# Tweetronic_Relay_Board.net
KiCad netlist of a schematic drawn in EAGLE
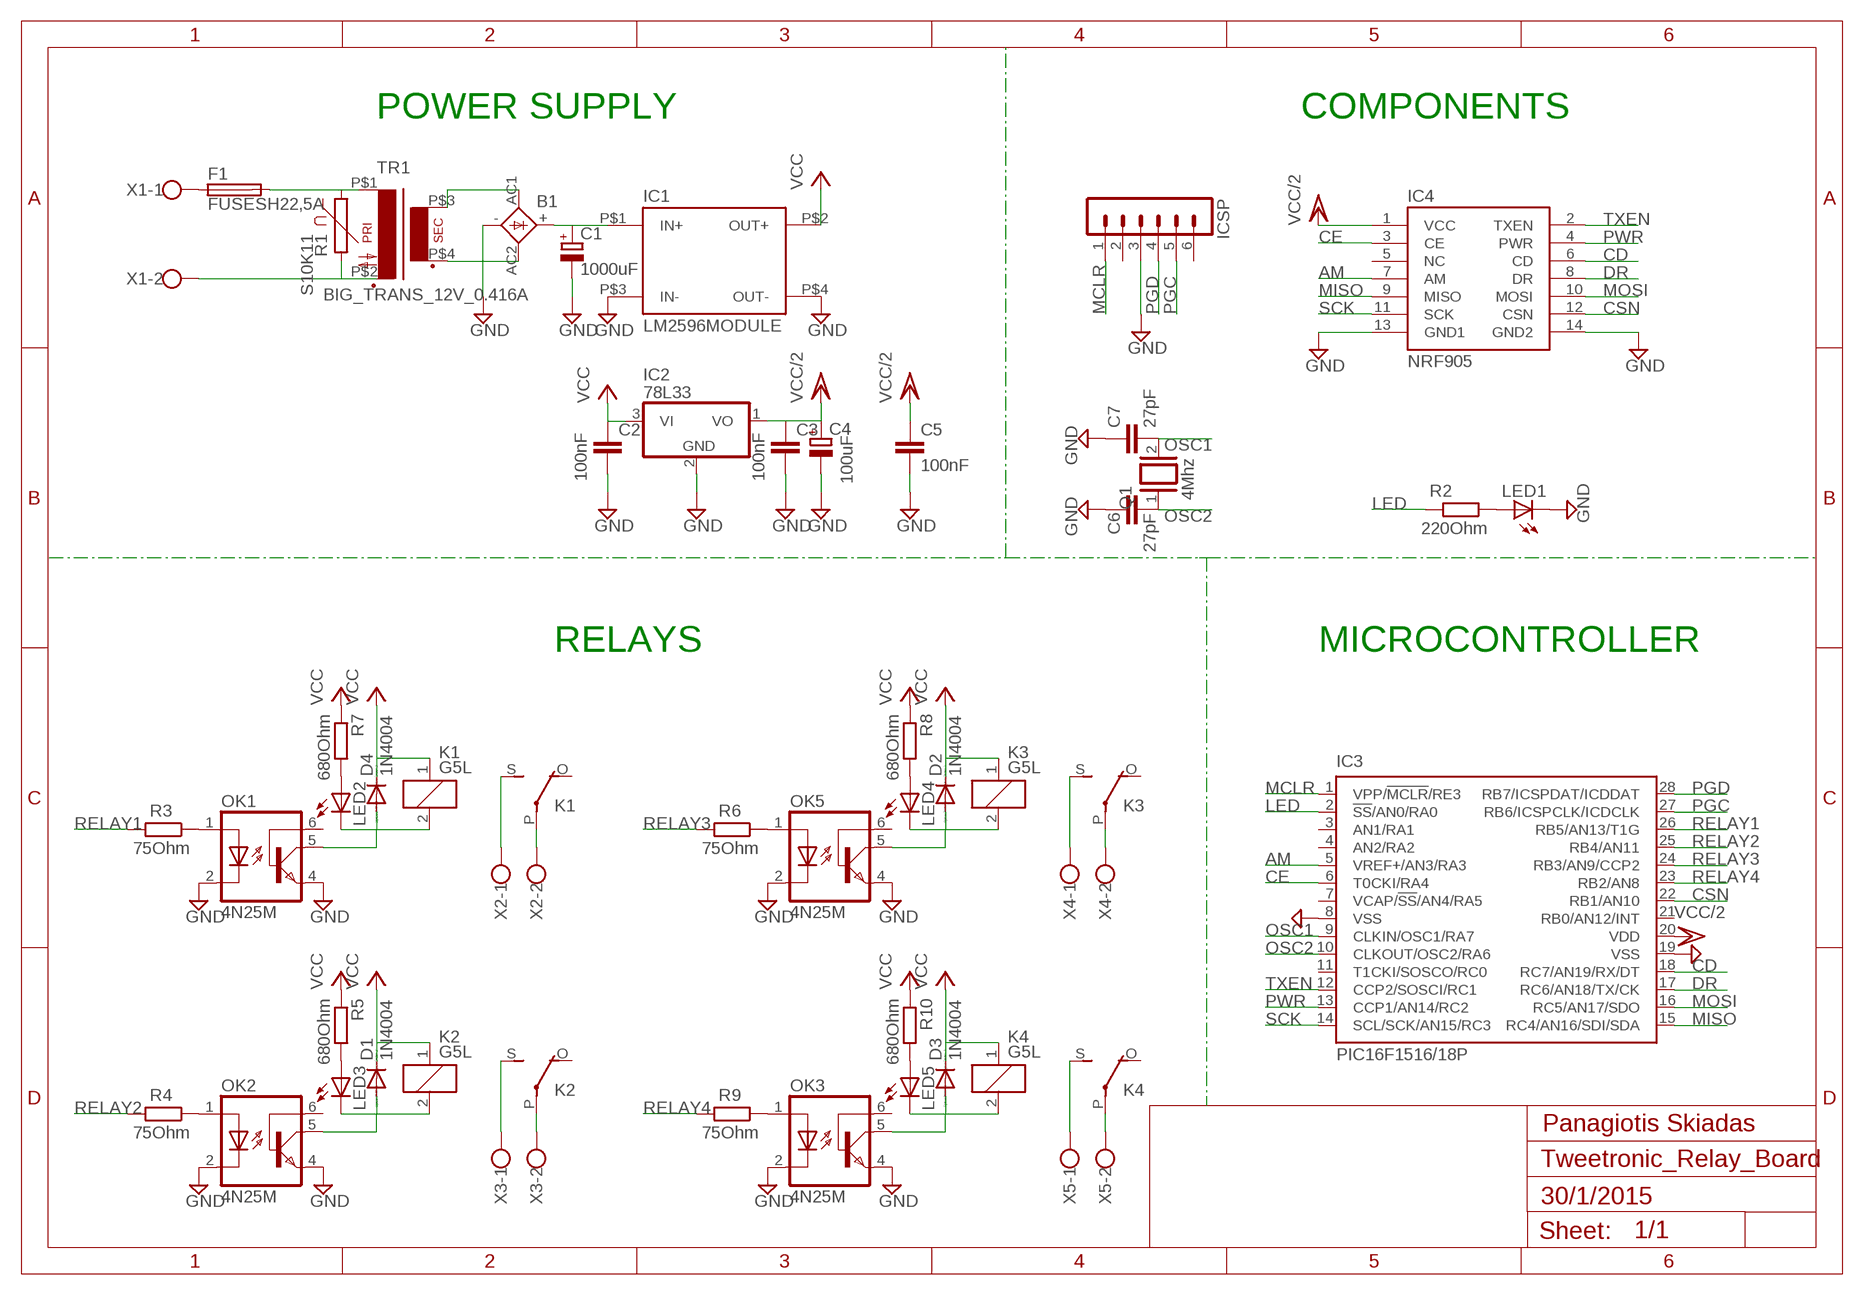
[diagram p0: schematic, sheet 1]

(export (version "E")
  (design (tool "Eeschema 10.0.6"))
  (components
    (comp (ref "B1")
      (value "1KAB")
      (footprint "eagle-import:1KAB")
      (libsource (lib "eagle-import") (part "1KAB"))
    )
    (comp (ref "C1")
      (value "1000uF")
      (footprint "eagle-import:E5-13")
      (libsource (lib "eagle-import") (part "CPOL-EUE5-13"))
    )
    (comp (ref "C2")
      (value "100nF")
      (footprint "eagle-import:C5B3")
      (libsource (lib "eagle-import") (part "C5/3"))
    )
    (comp (ref "C3")
      (value "100nF")
      (footprint "eagle-import:C5B3")
      (libsource (lib "eagle-import") (part "C5/3"))
    )
    (comp (ref "C4")
      (value "100uF")
      (footprint "eagle-import:E3,5-8")
      (libsource (lib "eagle-import") (part "CPOL-EUE3.5-8"))
    )
    (comp (ref "C5")
      (value "100nF")
      (footprint "eagle-import:C5B3")
      (libsource (lib "eagle-import") (part "C5/3"))
    )
    (comp (ref "C6")
      (value "27pF")
      (footprint "eagle-import:C2.5-3")
      (libsource (lib "eagle-import") (part "C2,5-3"))
    )
    (comp (ref "C7")
      (value "27pF")
      (footprint "eagle-import:C2.5-3")
      (libsource (lib "eagle-import") (part "C2,5-3"))
    )
    (comp (ref "D1")
      (value "1N4004")
      (footprint "eagle-import:DO41-10")
      (libsource (lib "eagle-import") (part "1N4004"))
    )
    (comp (ref "D2")
      (value "1N4004")
      (footprint "eagle-import:DO41-10")
      (libsource (lib "eagle-import") (part "1N4004"))
    )
    (comp (ref "D3")
      (value "1N4004")
      (footprint "eagle-import:DO41-10")
      (libsource (lib "eagle-import") (part "1N4004"))
    )
    (comp (ref "D4")
      (value "1N4004")
      (footprint "eagle-import:DO41-10")
      (libsource (lib "eagle-import") (part "1N4004"))
    )
    (comp (ref "F1")
      (value "FUSESH22,5A")
      (footprint "eagle-import:SH22,5A")
      (libsource (lib "eagle-import") (part "FUSESH22,5A"))
    )
    (comp (ref "IC1")
      (value "LM2596MODULE")
      (footprint "eagle-import:MODULE")
      (libsource (lib "eagle-import") (part "LM2596MODULE"))
    )
    (comp (ref "IC2")
      (value "78L33")
      (footprint "eagle-import:TO92")
      (libsource (lib "eagle-import") (part "78ZL05"))
    )
    (comp (ref "IC3")
      (value "PIC16F1516/18P")
      (footprint "eagle-import:DIL28-3")
      (libsource (lib "eagle-import") (part "PIC16F1516/18P"))
    )
    (comp (ref "IC4")
      (value "NRF905")
      (footprint "eagle-import:2X07")
      (libsource (lib "eagle-import") (part "NRF905"))
    )
    (comp (ref "ICSP")
      (value "MA06-1")
      (footprint "eagle-import:MA06-1")
      (libsource (lib "eagle-import") (part "MA06-1"))
    )
    (comp (ref "K1")
      (value "G5L")
      (footprint "eagle-import:G5LE")
      (libsource (lib "eagle-import") (part "G5L"))
    )
    (comp (ref "K2")
      (value "G5L")
      (footprint "eagle-import:G5LE")
      (libsource (lib "eagle-import") (part "G5L"))
    )
    (comp (ref "K3")
      (value "G5L")
      (footprint "eagle-import:G5LE")
      (libsource (lib "eagle-import") (part "G5L"))
    )
    (comp (ref "K4")
      (value "G5L")
      (footprint "eagle-import:G5LE")
      (libsource (lib "eagle-import") (part "G5L"))
    )
    (comp (ref "LED1")
      (value "LED5MM")
      (footprint "eagle-import:LED5MM")
      (libsource (lib "eagle-import") (part "LED5MM"))
    )
    (comp (ref "LED2")
      (value "LED3MM")
      (footprint "eagle-import:LED3MM")
      (libsource (lib "eagle-import") (part "LED3MM"))
    )
    (comp (ref "LED3")
      (value "LED3MM")
      (footprint "eagle-import:LED3MM")
      (libsource (lib "eagle-import") (part "LED3MM"))
    )
    (comp (ref "LED4")
      (value "LED3MM")
      (footprint "eagle-import:LED3MM")
      (libsource (lib "eagle-import") (part "LED3MM"))
    )
    (comp (ref "LED5")
      (value "LED3MM")
      (footprint "eagle-import:LED3MM")
      (libsource (lib "eagle-import") (part "LED3MM"))
    )
    (comp (ref "OK1")
      (value "4N25M")
      (footprint "eagle-import:DIL06")
      (fields (field (name "MPN") "4N25-M"))
      (libsource (lib "eagle-import") (part "4N?M25"))
    )
    (comp (ref "OK2")
      (value "4N25M")
      (footprint "eagle-import:DIL06")
      (fields (field (name "MPN") "4N25-M"))
      (libsource (lib "eagle-import") (part "4N?M25"))
    )
    (comp (ref "OK3")
      (value "4N25M")
      (footprint "eagle-import:DIL06")
      (fields (field (name "MPN") "4N25-M"))
      (libsource (lib "eagle-import") (part "4N?M25"))
    )
    (comp (ref "OK5")
      (value "4N25M")
      (footprint "eagle-import:DIL06")
      (fields (field (name "MPN") "4N25-M"))
      (libsource (lib "eagle-import") (part "4N?M25"))
    )
    (comp (ref "Q1")
      (value "4Mhz")
      (footprint "eagle-import:QS")
      (libsource (lib "eagle-import") (part "XTAL/S"))
    )
    (comp (ref "R1")
      (value "S10K11")
      (footprint "eagle-import:S10K11")
      (libsource (lib "eagle-import") (part "S10K11"))
    )
    (comp (ref "R2")
      (value "220Ohm")
      (footprint "eagle-import:0207_10")
      (libsource (lib "eagle-import") (part "R-EU_0207/10"))
    )
    (comp (ref "R3")
      (value "75Ohm")
      (footprint "eagle-import:0207_10")
      (libsource (lib "eagle-import") (part "R-EU_0207/10"))
    )
    (comp (ref "R4")
      (value "75Ohm")
      (footprint "eagle-import:0207_10")
      (libsource (lib "eagle-import") (part "R-EU_0207/10"))
    )
    (comp (ref "R5")
      (value "680Ohm")
      (footprint "eagle-import:0207_10")
      (libsource (lib "eagle-import") (part "R-EU_0207/10"))
    )
    (comp (ref "R6")
      (value "75Ohm")
      (footprint "eagle-import:0207_10")
      (libsource (lib "eagle-import") (part "R-EU_0207/10"))
    )
    (comp (ref "R7")
      (value "680Ohm")
      (footprint "eagle-import:0207_10")
      (libsource (lib "eagle-import") (part "R-EU_0207/10"))
    )
    (comp (ref "R8")
      (value "680Ohm")
      (footprint "eagle-import:0207_10")
      (libsource (lib "eagle-import") (part "R-EU_0207/10"))
    )
    (comp (ref "R9")
      (value "75Ohm")
      (footprint "eagle-import:0207_10")
      (libsource (lib "eagle-import") (part "R-EU_0207/10"))
    )
    (comp (ref "R10")
      (value "680Ohm")
      (footprint "eagle-import:0207_10")
      (libsource (lib "eagle-import") (part "R-EU_0207/10"))
    )
    (comp (ref "TR1")
      (value "BIG_TRANS_12V_0.416A")
      (footprint "eagle-import:BIG_TRANSF_12V_0.416A")
      (libsource (lib "eagle-import") (part "BIG_TRANS_12V_0.416A"))
    )
    (comp (ref "X1")
      (value "W237-102")
      (footprint "eagle-import:W237-102")
      (fields (field (name "MPN") "237-102"))
      (libsource (lib "eagle-import") (part "W237-102"))
    )
    (comp (ref "X2")
      (value "W237-102")
      (footprint "eagle-import:W237-102")
      (fields (field (name "MPN") "237-102"))
      (libsource (lib "eagle-import") (part "W237-102"))
    )
    (comp (ref "X3")
      (value "W237-102")
      (footprint "eagle-import:W237-102")
      (fields (field (name "MPN") "237-102"))
      (libsource (lib "eagle-import") (part "W237-102"))
    )
    (comp (ref "X4")
      (value "W237-102")
      (footprint "eagle-import:W237-102")
      (fields (field (name "MPN") "237-102"))
      (libsource (lib "eagle-import") (part "W237-102"))
    )
    (comp (ref "X5")
      (value "W237-102")
      (footprint "eagle-import:W237-102")
      (fields (field (name "MPN") "237-102"))
      (libsource (lib "eagle-import") (part "W237-102"))
    )
  )
  (nets
    (net (code "1") (name "/AM") (class "Default")
      (node (ref "IC3") (pin "5") (pinfunction "VREF+/AN3/RA3_5") (pintype "bidirectional"))
      (node (ref "IC4") (pin "7") (pinfunction "AM_7") (pintype "bidirectional"))
    )
    (net (code "2") (name "/CD") (class "Default")
      (node (ref "IC3") (pin "18") (pinfunction "RC7/AN19/RX/DT_18") (pintype "bidirectional"))
      (node (ref "IC4") (pin "6") (pinfunction "CD_6") (pintype "bidirectional"))
    )
    (net (code "3") (name "/CE") (class "Default")
      (node (ref "IC3") (pin "6") (pinfunction "T0CKI/RA4_6") (pintype "bidirectional"))
      (node (ref "IC4") (pin "3") (pinfunction "CE_3") (pintype "bidirectional"))
    )
    (net (code "4") (name "/CSN") (class "Default")
      (node (ref "IC3") (pin "22") (pinfunction "RB1/AN10_22") (pintype "bidirectional"))
      (node (ref "IC4") (pin "12") (pinfunction "CSN_12") (pintype "bidirectional"))
    )
    (net (code "5") (name "/DR") (class "Default")
      (node (ref "IC3") (pin "17") (pinfunction "RC6/AN18/TX/CK_17") (pintype "bidirectional"))
      (node (ref "IC4") (pin "8") (pinfunction "DR_8") (pintype "bidirectional"))
    )
    (net (code "6") (name "/LED") (class "Default")
      (node (ref "IC3") (pin "2") (pinfunction "~{SS}/AN0/RA0_2") (pintype "bidirectional"))
      (node (ref "R2") (pin "2") (pinfunction "2_2") (pintype "passive"))
    )
    (net (code "7") (name "/MCLR") (class "Default")
      (node (ref "IC3") (pin "1") (pinfunction "VPP/~{MCLR}/RE3_1") (pintype "bidirectional"))
      (node (ref "ICSP") (pin "1") (pinfunction "1_1") (pintype "passive"))
    )
    (net (code "8") (name "/MISO") (class "Default")
      (node (ref "IC3") (pin "15") (pinfunction "RC4/AN16/SDI/SDA_15") (pintype "bidirectional"))
      (node (ref "IC4") (pin "9") (pinfunction "MISO_9") (pintype "bidirectional"))
    )
    (net (code "9") (name "/MOSI") (class "Default")
      (node (ref "IC3") (pin "16") (pinfunction "RC5/AN17/SDO_16") (pintype "bidirectional"))
      (node (ref "IC4") (pin "10") (pinfunction "MOSI_10") (pintype "bidirectional"))
    )
    (net (code "10") (name "/OSC1") (class "Default")
      (node (ref "C7") (pin "2") (pinfunction "2_2") (pintype "passive"))
      (node (ref "IC3") (pin "9") (pinfunction "CLKIN/OSC1/RA7_9") (pintype "bidirectional"))
      (node (ref "Q1") (pin "2") (pinfunction "2_2") (pintype "passive"))
    )
    (net (code "11") (name "/OSC2") (class "Default")
      (node (ref "C6") (pin "2") (pinfunction "2_2") (pintype "passive"))
      (node (ref "IC3") (pin "10") (pinfunction "CLKOUT/OSC2/RA6_10") (pintype "bidirectional"))
      (node (ref "Q1") (pin "1") (pinfunction "1_1") (pintype "passive"))
    )
    (net (code "12") (name "/PGC") (class "Default")
      (node (ref "IC3") (pin "27") (pinfunction "RB6/ICSPCLK/ICDCLK_27") (pintype "bidirectional"))
      (node (ref "ICSP") (pin "5") (pinfunction "5_5") (pintype "passive"))
    )
    (net (code "13") (name "/PGD") (class "Default")
      (node (ref "IC3") (pin "28") (pinfunction "RB7/ICSPDAT/ICDDAT_28") (pintype "bidirectional"))
      (node (ref "ICSP") (pin "4") (pinfunction "4_4") (pintype "passive"))
    )
    (net (code "14") (name "/PWR") (class "Default")
      (node (ref "IC3") (pin "13") (pinfunction "CCP1/AN14/RC2_13") (pintype "bidirectional"))
      (node (ref "IC4") (pin "4") (pinfunction "PWR_4") (pintype "bidirectional"))
    )
    (net (code "15") (name "/RELAY1") (class "Default")
      (node (ref "IC3") (pin "26") (pinfunction "RB5/AN13/T1G_26") (pintype "bidirectional"))
      (node (ref "R3") (pin "2") (pinfunction "2_2") (pintype "passive"))
    )
    (net (code "16") (name "/RELAY2") (class "Default")
      (node (ref "IC3") (pin "25") (pinfunction "RB4/AN11_25") (pintype "bidirectional"))
      (node (ref "R4") (pin "2") (pinfunction "2_2") (pintype "passive"))
    )
    (net (code "17") (name "/RELAY3") (class "Default")
      (node (ref "IC3") (pin "24") (pinfunction "RB3/AN9/CCP2_24") (pintype "bidirectional"))
      (node (ref "R6") (pin "2") (pinfunction "2_2") (pintype "passive"))
    )
    (net (code "18") (name "/RELAY4") (class "Default")
      (node (ref "IC3") (pin "23") (pinfunction "RB2/AN8_23") (pintype "bidirectional"))
      (node (ref "R9") (pin "2") (pinfunction "2_2") (pintype "passive"))
    )
    (net (code "19") (name "/SCK") (class "Default")
      (node (ref "IC3") (pin "14") (pinfunction "SCL/SCK/AN15/RC3_14") (pintype "bidirectional"))
      (node (ref "IC4") (pin "11") (pinfunction "SCK_11") (pintype "bidirectional"))
    )
    (net (code "20") (name "/TXEN") (class "Default")
      (node (ref "IC3") (pin "12") (pinfunction "CCP2/SOSCI/RC1_12") (pintype "bidirectional"))
      (node (ref "IC4") (pin "2") (pinfunction "TXEN_2") (pintype "bidirectional"))
    )
    (net (code "21") (name "GND") (class "Default")
      (node (ref "B1") (pin "-") (pinfunction "-_-") (pintype "passive"))
      (node (ref "C1") (pin "-") (pinfunction "-_-") (pintype "passive"))
      (node (ref "C2") (pin "2") (pinfunction "2_2") (pintype "passive"))
      (node (ref "C3") (pin "2") (pinfunction "2_2") (pintype "passive"))
      (node (ref "C4") (pin "-") (pinfunction "-_-") (pintype "passive"))
      (node (ref "C5") (pin "2") (pinfunction "2_2") (pintype "passive"))
      (node (ref "C6") (pin "1") (pinfunction "1_1") (pintype "passive"))
      (node (ref "C7") (pin "1") (pinfunction "1_1") (pintype "passive"))
      (node (ref "IC1") (pin "P$3") (pinfunction "IN-_P$3") (pintype "bidirectional"))
      (node (ref "IC1") (pin "P$4") (pinfunction "OUT-_P$4") (pintype "bidirectional"))
      (node (ref "IC2") (pin "2") (pinfunction "GND_2") (pintype "passive"))
      (node (ref "IC3") (pin "19") (pinfunction "VSS_19") (pintype "power_in"))
      (node (ref "IC3") (pin "8") (pinfunction "VSS_8") (pintype "power_in"))
      (node (ref "IC4") (pin "13") (pinfunction "GND1_13") (pintype "bidirectional"))
      (node (ref "IC4") (pin "14") (pinfunction "GND2_14") (pintype "bidirectional"))
      (node (ref "ICSP") (pin "3") (pinfunction "3_3") (pintype "passive"))
      (node (ref "LED1") (pin "K") (pinfunction "C_K") (pintype "passive"))
      (node (ref "OK1") (pin "2") (pinfunction "C_2") (pintype "passive"))
      (node (ref "OK1") (pin "4") (pinfunction "EMI_4") (pintype "passive"))
      (node (ref "OK2") (pin "2") (pinfunction "C_2") (pintype "passive"))
      (node (ref "OK2") (pin "4") (pinfunction "EMI_4") (pintype "passive"))
      (node (ref "OK3") (pin "2") (pinfunction "C_2") (pintype "passive"))
      (node (ref "OK3") (pin "4") (pinfunction "EMI_4") (pintype "passive"))
      (node (ref "OK5") (pin "2") (pinfunction "C_2") (pintype "passive"))
      (node (ref "OK5") (pin "4") (pinfunction "EMI_4") (pintype "passive"))
    )
    (net (code "22") (name "Net-(IC1-IN+)") (class "Default")
      (node (ref "B1") (pin "+") (pinfunction "+_+") (pintype "passive"))
      (node (ref "C1") (pin "+") (pinfunction "+_+") (pintype "passive"))
      (node (ref "IC1") (pin "P$1") (pinfunction "IN+_P$1") (pintype "bidirectional"))
    )
    (net (code "23") (name "Net-(LED1-PadA)") (class "Default")
      (node (ref "LED1") (pin "A") (pinfunction "A_A") (pintype "passive"))
      (node (ref "R2") (pin "1") (pinfunction "1_1") (pintype "passive"))
    )
    (net (code "24") (name "Net-(LED2-C)") (class "Default")
      (node (ref "D4") (pin "A") (pinfunction "A_A") (pintype "passive"))
      (node (ref "K1") (pin "2") (pinfunction "2_2") (pintype "passive"))
      (node (ref "LED2") (pin "K") (pinfunction "C_K") (pintype "passive"))
      (node (ref "OK1") (pin "5") (pinfunction "COL_5") (pintype "passive"))
    )
    (net (code "25") (name "Net-(LED2-PadA)") (class "Default")
      (node (ref "LED2") (pin "A") (pinfunction "A_A") (pintype "passive"))
      (node (ref "R7") (pin "2") (pinfunction "2_2") (pintype "passive"))
    )
    (net (code "26") (name "Net-(LED3-C)") (class "Default")
      (node (ref "D1") (pin "A") (pinfunction "A_A") (pintype "passive"))
      (node (ref "K2") (pin "2") (pinfunction "2_2") (pintype "passive"))
      (node (ref "LED3") (pin "K") (pinfunction "C_K") (pintype "passive"))
      (node (ref "OK2") (pin "5") (pinfunction "COL_5") (pintype "passive"))
    )
    (net (code "27") (name "Net-(LED3-PadA)") (class "Default")
      (node (ref "LED3") (pin "A") (pinfunction "A_A") (pintype "passive"))
      (node (ref "R5") (pin "2") (pinfunction "2_2") (pintype "passive"))
    )
    (net (code "28") (name "Net-(LED4-C)") (class "Default")
      (node (ref "D2") (pin "A") (pinfunction "A_A") (pintype "passive"))
      (node (ref "K3") (pin "2") (pinfunction "2_2") (pintype "passive"))
      (node (ref "LED4") (pin "K") (pinfunction "C_K") (pintype "passive"))
      (node (ref "OK5") (pin "5") (pinfunction "COL_5") (pintype "passive"))
    )
    (net (code "29") (name "Net-(LED4-PadA)") (class "Default")
      (node (ref "LED4") (pin "A") (pinfunction "A_A") (pintype "passive"))
      (node (ref "R8") (pin "2") (pinfunction "2_2") (pintype "passive"))
    )
    (net (code "30") (name "Net-(LED5-C)") (class "Default")
      (node (ref "D3") (pin "A") (pinfunction "A_A") (pintype "passive"))
      (node (ref "K4") (pin "2") (pinfunction "2_2") (pintype "passive"))
      (node (ref "LED5") (pin "K") (pinfunction "C_K") (pintype "passive"))
      (node (ref "OK3") (pin "5") (pinfunction "COL_5") (pintype "passive"))
    )
    (net (code "31") (name "Net-(LED5-PadA)") (class "Default")
      (node (ref "LED5") (pin "A") (pinfunction "A_A") (pintype "passive"))
      (node (ref "R10") (pin "2") (pinfunction "2_2") (pintype "passive"))
    )
    (net (code "32") (name "Net-(OK1-A)") (class "Default")
      (node (ref "OK1") (pin "1") (pinfunction "A_1") (pintype "passive"))
      (node (ref "R3") (pin "1") (pinfunction "1_1") (pintype "passive"))
    )
    (net (code "33") (name "Net-(OK2-A)") (class "Default")
      (node (ref "OK2") (pin "1") (pinfunction "A_1") (pintype "passive"))
      (node (ref "R4") (pin "1") (pinfunction "1_1") (pintype "passive"))
    )
    (net (code "34") (name "Net-(OK3-A)") (class "Default")
      (node (ref "OK3") (pin "1") (pinfunction "A_1") (pintype "passive"))
      (node (ref "R9") (pin "1") (pinfunction "1_1") (pintype "passive"))
    )
    (net (code "35") (name "Net-(OK5-A)") (class "Default")
      (node (ref "OK5") (pin "1") (pinfunction "A_1") (pintype "passive"))
      (node (ref "R6") (pin "1") (pinfunction "1_1") (pintype "passive"))
    )
    (net (code "36") (name "Net-(TR1-P1)") (class "Default")
      (node (ref "F1") (pin "2") (pinfunction "2_2") (pintype "passive"))
      (node (ref "R1") (pin "1") (pinfunction "1_1") (pintype "passive"))
      (node (ref "TR1") (pin "P$1") (pinfunction "P1_P$1") (pintype "passive"))
    )
    (net (code "37") (name "Net-(TR1-P2)") (class "Default")
      (node (ref "R1") (pin "2") (pinfunction "2_2") (pintype "passive"))
      (node (ref "TR1") (pin "P$2") (pinfunction "P2_P$2") (pintype "passive"))
      (node (ref "X1") (pin "2") (pinfunction "KL_2") (pintype "passive"))
    )
    (net (code "38") (name "Net-(TR1-S3)") (class "Default")
      (node (ref "B1") (pin "AC2") (pinfunction "AC2_AC2") (pintype "passive"))
      (node (ref "TR1") (pin "P$4") (pinfunction "S3_P$4") (pintype "passive"))
    )
    (net (code "39") (name "Net-(TR1-S4)") (class "Default")
      (node (ref "B1") (pin "AC1") (pinfunction "AC1_AC1") (pintype "passive"))
      (node (ref "TR1") (pin "P$3") (pinfunction "S4_P$3") (pintype "passive"))
    )
    (net (code "40") (name "Net-(X1A-KL)") (class "Default")
      (node (ref "F1") (pin "1") (pinfunction "1_1") (pintype "passive"))
      (node (ref "X1") (pin "1") (pinfunction "KL_1") (pintype "passive"))
    )
    (net (code "41") (name "Net-(X2A-KL)") (class "Default")
      (node (ref "K1") (pin "S") (pinfunction "S_S") (pintype "passive"))
      (node (ref "X2") (pin "1") (pinfunction "KL_1") (pintype "passive"))
    )
    (net (code "42") (name "Net-(X2B-KL)") (class "Default")
      (node (ref "K1") (pin "P") (pinfunction "P_P") (pintype "passive"))
      (node (ref "X2") (pin "2") (pinfunction "KL_2") (pintype "passive"))
    )
    (net (code "43") (name "Net-(X3A-KL)") (class "Default")
      (node (ref "K2") (pin "S") (pinfunction "S_S") (pintype "passive"))
      (node (ref "X3") (pin "1") (pinfunction "KL_1") (pintype "passive"))
    )
    (net (code "44") (name "Net-(X3B-KL)") (class "Default")
      (node (ref "K2") (pin "P") (pinfunction "P_P") (pintype "passive"))
      (node (ref "X3") (pin "2") (pinfunction "KL_2") (pintype "passive"))
    )
    (net (code "45") (name "Net-(X4A-KL)") (class "Default")
      (node (ref "K3") (pin "S") (pinfunction "S_S") (pintype "passive"))
      (node (ref "X4") (pin "1") (pinfunction "KL_1") (pintype "passive"))
    )
    (net (code "46") (name "Net-(X4B-KL)") (class "Default")
      (node (ref "K3") (pin "P") (pinfunction "P_P") (pintype "passive"))
      (node (ref "X4") (pin "2") (pinfunction "KL_2") (pintype "passive"))
    )
    (net (code "47") (name "Net-(X5A-KL)") (class "Default")
      (node (ref "K4") (pin "S") (pinfunction "S_S") (pintype "passive"))
      (node (ref "X5") (pin "1") (pinfunction "KL_1") (pintype "passive"))
    )
    (net (code "48") (name "Net-(X5B-KL)") (class "Default")
      (node (ref "K4") (pin "P") (pinfunction "P_P") (pintype "passive"))
      (node (ref "X5") (pin "2") (pinfunction "KL_2") (pintype "passive"))
    )
    (net (code "49") (name "VCC") (class "Default")
      (node (ref "C2") (pin "1") (pinfunction "1_1") (pintype "passive"))
      (node (ref "D1") (pin "C") (pinfunction "C_C") (pintype "passive"))
      (node (ref "D2") (pin "C") (pinfunction "C_C") (pintype "passive"))
      (node (ref "D3") (pin "C") (pinfunction "C_C") (pintype "passive"))
      (node (ref "D4") (pin "C") (pinfunction "C_C") (pintype "passive"))
      (node (ref "IC1") (pin "P$2") (pinfunction "OUT+_P$2") (pintype "bidirectional"))
      (node (ref "IC2") (pin "3") (pinfunction "VI_3") (pintype "input"))
      (node (ref "K1") (pin "1") (pinfunction "1_1") (pintype "passive"))
      (node (ref "K2") (pin "1") (pinfunction "1_1") (pintype "passive"))
      (node (ref "K3") (pin "1") (pinfunction "1_1") (pintype "passive"))
      (node (ref "K4") (pin "1") (pinfunction "1_1") (pintype "passive"))
      (node (ref "R10") (pin "1") (pinfunction "1_1") (pintype "passive"))
      (node (ref "R5") (pin "1") (pinfunction "1_1") (pintype "passive"))
      (node (ref "R7") (pin "1") (pinfunction "1_1") (pintype "passive"))
      (node (ref "R8") (pin "1") (pinfunction "1_1") (pintype "passive"))
    )
    (net (code "50") (name "VCC{slash}2") (class "Default")
      (node (ref "C3") (pin "1") (pinfunction "1_1") (pintype "passive"))
      (node (ref "C4") (pin "+") (pinfunction "+_+") (pintype "passive"))
      (node (ref "C5") (pin "1") (pinfunction "1_1") (pintype "passive"))
      (node (ref "IC2") (pin "1") (pinfunction "VO_1") (pintype "passive"))
      (node (ref "IC3") (pin "20") (pinfunction "VDD_20") (pintype "power_in"))
      (node (ref "IC4") (pin "1") (pinfunction "VCC_1") (pintype "bidirectional"))
    )
    (net (code "51") (name "unconnected-(IC3-AN1{slash}RA1-Pad3)") (class "Default")
      (node (ref "IC3") (pin "3") (pinfunction "AN1/RA1_3") (pintype "bidirectional"))
    )
    (net (code "52") (name "unconnected-(IC3-AN2{slash}RA2-Pad4)") (class "Default")
      (node (ref "IC3") (pin "4") (pinfunction "AN2/RA2_4") (pintype "bidirectional"))
    )
    (net (code "53") (name "unconnected-(IC3-RB0{slash}AN12{slash}INT-Pad21)") (class "Default")
      (node (ref "IC3") (pin "21") (pinfunction "RB0/AN12/INT_21") (pintype "bidirectional"))
    )
    (net (code "54") (name "unconnected-(IC3-T1CKI{slash}SOSCO{slash}RC0-Pad11)") (class "Default")
      (node (ref "IC3") (pin "11") (pinfunction "T1CKI/SOSCO/RC0_11") (pintype "bidirectional"))
    )
    (net (code "55") (name "unconnected-(IC3-VCAP{slash}~{SS}{slash}AN4{slash}RA5-Pad7)") (class "Default")
      (node (ref "IC3") (pin "7") (pinfunction "VCAP/~{SS}/AN4/RA5_7") (pintype "bidirectional"))
    )
    (net (code "56") (name "unconnected-(IC4-NC-Pad5)") (class "Default")
      (node (ref "IC4") (pin "5") (pinfunction "NC_5") (pintype "bidirectional"))
    )
    (net (code "57") (name "unconnected-(ICSP-Pad2)") (class "Default")
      (node (ref "ICSP") (pin "2") (pinfunction "2_2") (pintype "passive"))
    )
    (net (code "58") (name "unconnected-(ICSP-Pad6)") (class "Default")
      (node (ref "ICSP") (pin "6") (pinfunction "6_6") (pintype "passive"))
    )
    (net (code "59") (name "unconnected-(K1-PadO)") (class "Default")
      (node (ref "K1") (pin "O") (pinfunction "O_O") (pintype "passive"))
    )
    (net (code "60") (name "unconnected-(K2-PadO)") (class "Default")
      (node (ref "K2") (pin "O") (pinfunction "O_O") (pintype "passive"))
    )
    (net (code "61") (name "unconnected-(K3-PadO)") (class "Default")
      (node (ref "K3") (pin "O") (pinfunction "O_O") (pintype "passive"))
    )
    (net (code "62") (name "unconnected-(K4-PadO)") (class "Default")
      (node (ref "K4") (pin "O") (pinfunction "O_O") (pintype "passive"))
    )
    (net (code "63") (name "unconnected-(OK1-BAS-Pad6)") (class "Default")
      (node (ref "OK1") (pin "6") (pinfunction "BAS_6") (pintype "passive"))
    )
    (net (code "64") (name "unconnected-(OK2-BAS-Pad6)") (class "Default")
      (node (ref "OK2") (pin "6") (pinfunction "BAS_6") (pintype "passive"))
    )
    (net (code "65") (name "unconnected-(OK3-BAS-Pad6)") (class "Default")
      (node (ref "OK3") (pin "6") (pinfunction "BAS_6") (pintype "passive"))
    )
    (net (code "66") (name "unconnected-(OK5-BAS-Pad6)") (class "Default")
      (node (ref "OK5") (pin "6") (pinfunction "BAS_6") (pintype "passive"))
    )
  )
)
